# neue_schaltung.net
KiCad netlist of a schematic drawn in EAGLE
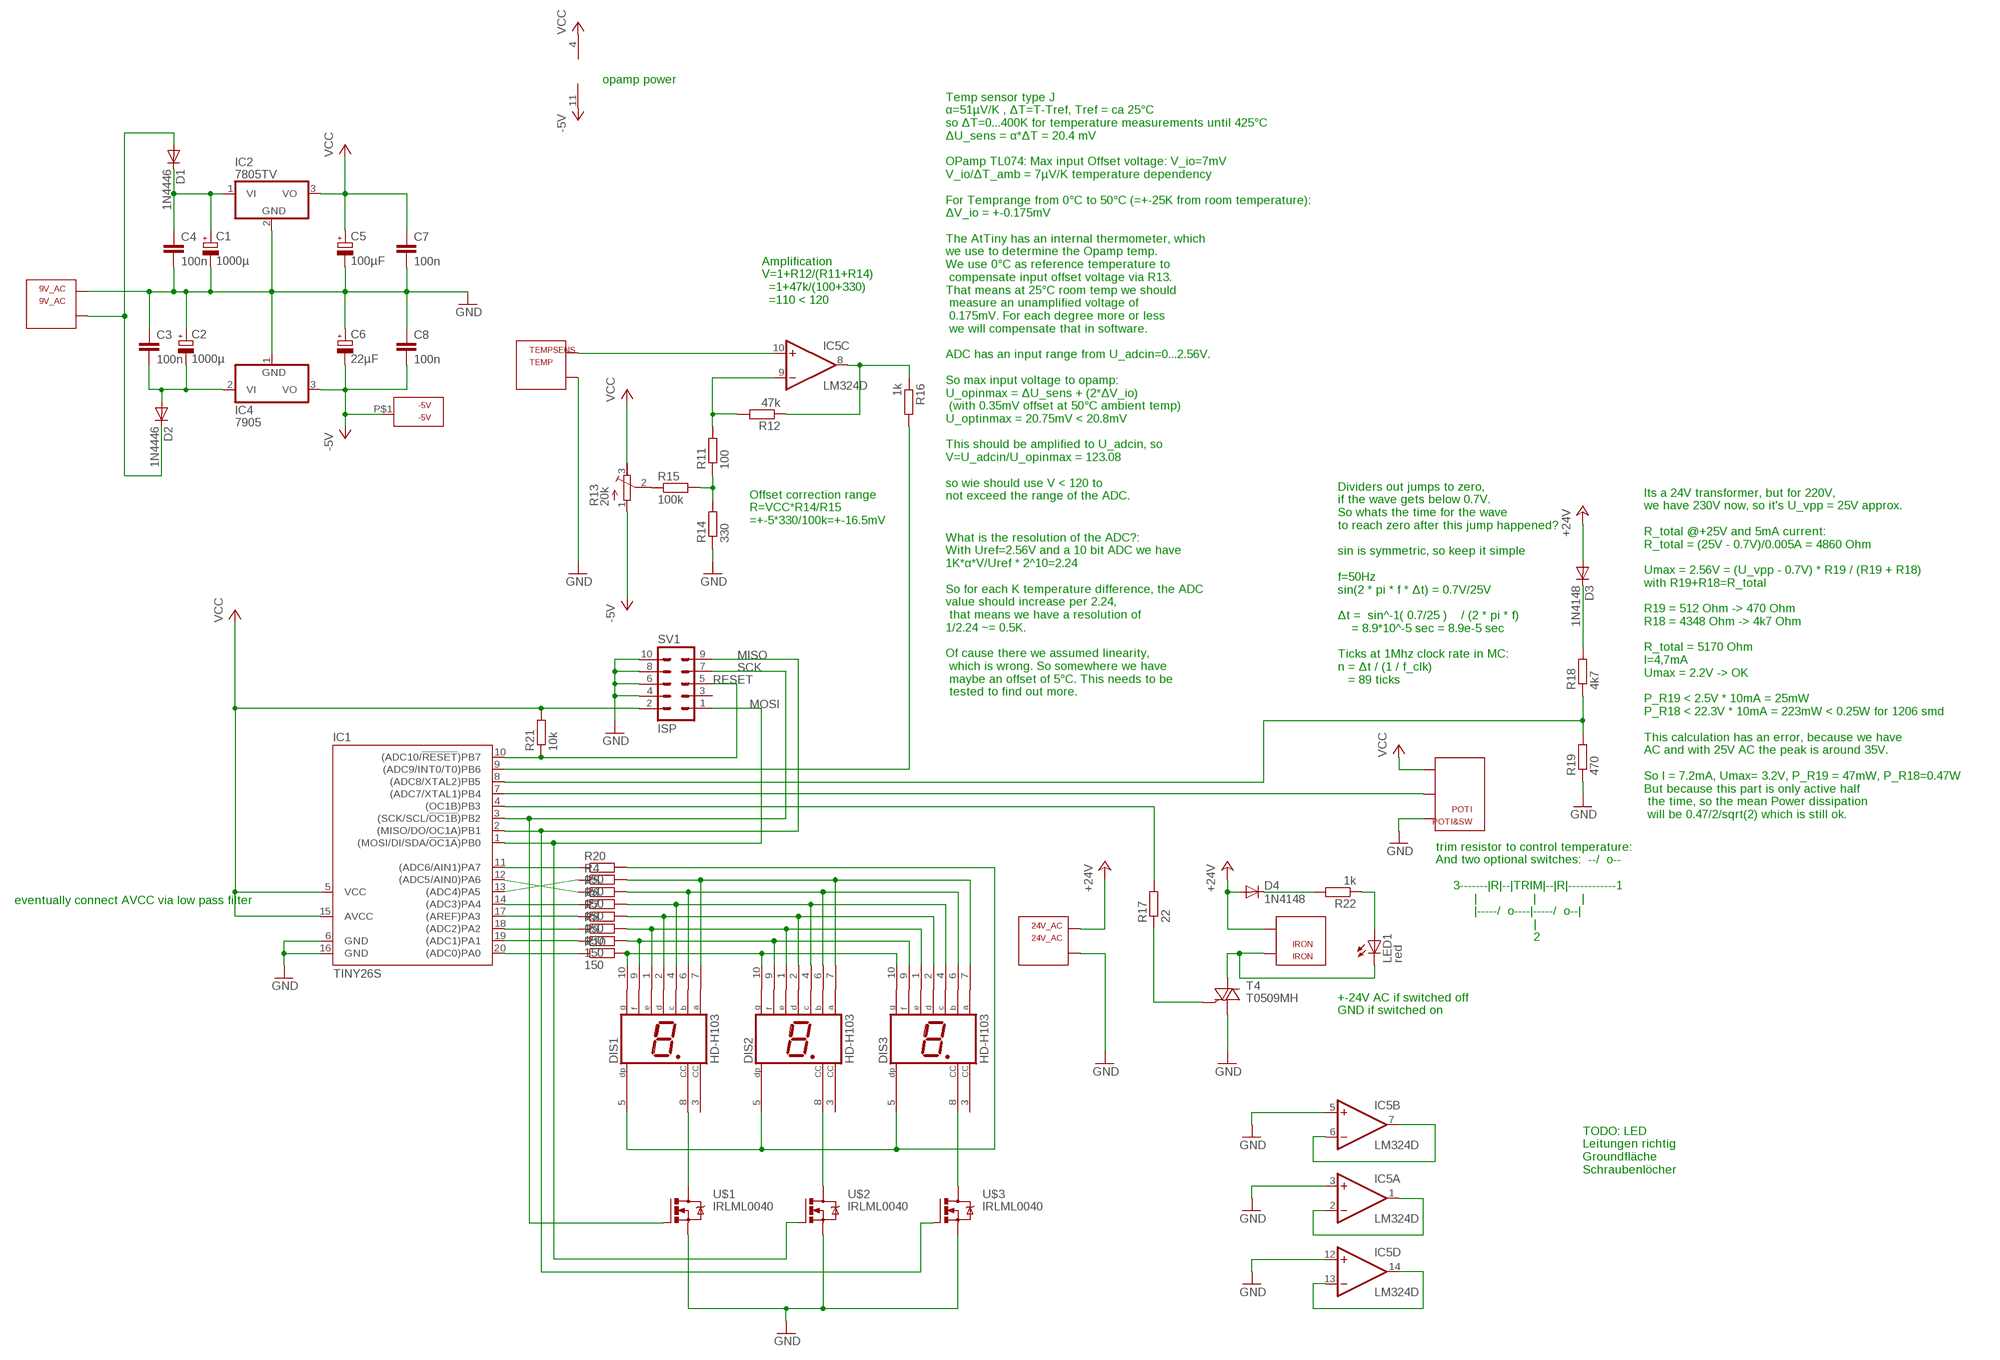
[diagram p0: schematic, sheet 1]

(export (version "E")
  (design (tool "Eeschema 10.0.6"))
  (components
    (comp (ref "-5V")
      (value "-5V")
      (footprint "eagle-import:WIREPAD_2H")
      (libsource (lib "eagle-import") (part "WIREPAD"))
    )
    (comp (ref "9V_AC")
      (value "9V_AC")
      (footprint "eagle-import:WIREPADX2_2H")
      (libsource (lib "eagle-import") (part "WIREPADX2"))
    )
    (comp (ref "24V_AC")
      (value "24V_AC")
      (footprint "eagle-import:WIREPADX2_2H_BIG")
      (libsource (lib "eagle-import") (part "WIREPADX2_BIG"))
    )
    (comp (ref "C1")
      (value "1000µ")
      (footprint "eagle-import:E5-10,5")
      (libsource (lib "eagle-import") (part "CPOL-EUE5-10.5"))
    )
    (comp (ref "C2")
      (value "1000µ")
      (footprint "eagle-import:E5-10,5")
      (libsource (lib "eagle-import") (part "CPOL-EUE5-10.5"))
    )
    (comp (ref "C3")
      (value "100n")
      (footprint "eagle-import:C0805")
      (libsource (lib "eagle-import") (part "C-EUC0805"))
    )
    (comp (ref "C4")
      (value "100n")
      (footprint "eagle-import:C0805")
      (libsource (lib "eagle-import") (part "C-EUC0805"))
    )
    (comp (ref "C5")
      (value "100µF")
      (footprint "eagle-import:E2-5")
      (libsource (lib "eagle-import") (part "CPOL-EUE2-5"))
    )
    (comp (ref "C6")
      (value "22µF")
      (footprint "eagle-import:E2-5")
      (libsource (lib "eagle-import") (part "CPOL-EUE2-5"))
    )
    (comp (ref "C7")
      (value "100n")
      (footprint "eagle-import:C0805")
      (libsource (lib "eagle-import") (part "C-EUC0805"))
    )
    (comp (ref "C8")
      (value "100n")
      (footprint "eagle-import:C0805")
      (libsource (lib "eagle-import") (part "C-EUC0805"))
    )
    (comp (ref "D1")
      (value "1N4446")
      (footprint "eagle-import:DO35-10")
      (libsource (lib "eagle-import") (part "1N4446"))
    )
    (comp (ref "D2")
      (value "1N4446")
      (footprint "eagle-import:DO35-10")
      (libsource (lib "eagle-import") (part "1N4446"))
    )
    (comp (ref "D3")
      (value "1N4148")
      (footprint "eagle-import:DO35-10")
      (libsource (lib "eagle-import") (part "1N4148DO35-10"))
    )
    (comp (ref "D4")
      (value "1N4148")
      (footprint "eagle-import:DO35-10")
      (libsource (lib "eagle-import") (part "1N4148DO35-10"))
    )
    (comp (ref "DIS1")
      (value "HD-H103")
      (footprint "eagle-import:HDSP-M")
      (libsource (lib "eagle-import") (part "HD-H103"))
    )
    (comp (ref "DIS2")
      (value "HD-H103")
      (footprint "eagle-import:HDSP-M")
      (libsource (lib "eagle-import") (part "HD-H103"))
    )
    (comp (ref "DIS3")
      (value "HD-H103")
      (footprint "eagle-import:HDSP-M")
      (libsource (lib "eagle-import") (part "HD-H103"))
    )
    (comp (ref "IC1")
      (value "TINY26S")
      (footprint "eagle-import:SO20L")
      (fields (field (name "MPN") "ATTINY261-20SU"))
      (libsource (lib "eagle-import") (part "TINY26S"))
    )
    (comp (ref "IC2")
      (value "7805TV")
      (footprint "eagle-import:TO220V")
      (libsource (lib "eagle-import") (part "78TV05"))
    )
    (comp (ref "IC4")
      (value "7905")
      (footprint "eagle-import:TO220H")
      (libsource (lib "eagle-import") (part "79T05"))
    )
    (comp (ref "IC5")
      (value "LM324D")
      (footprint "eagle-import:SO14")
      (libsource (lib "eagle-import") (part "LM324D"))
    )
    (comp (ref "IRON")
      (value "IRON")
      (footprint "eagle-import:WIREPADX2_2H_BIG")
      (libsource (lib "eagle-import") (part "WIREPADX2_BIG"))
    )
    (comp (ref "LED1")
      (value "red")
      (footprint "eagle-import:LED5MM")
      (libsource (lib "eagle-import") (part "LED5MM"))
    )
    (comp (ref "POTI&SW")
      (value "POTI")
      (footprint "eagle-import:WIREPADX3_2H")
      (libsource (lib "eagle-import") (part "WIREPADX3"))
    )
    (comp (ref "R4")
      (value "150")
      (footprint "eagle-import:M1206")
      (libsource (lib "eagle-import") (part "R-EU_M1206"))
    )
    (comp (ref "R5")
      (value "150")
      (footprint "eagle-import:M1206")
      (libsource (lib "eagle-import") (part "R-EU_M1206"))
    )
    (comp (ref "R6")
      (value "150")
      (footprint "eagle-import:M1206")
      (libsource (lib "eagle-import") (part "R-EU_M1206"))
    )
    (comp (ref "R7")
      (value "150")
      (footprint "eagle-import:M1206")
      (libsource (lib "eagle-import") (part "R-EU_M1206"))
    )
    (comp (ref "R8")
      (value "150")
      (footprint "eagle-import:M1206")
      (libsource (lib "eagle-import") (part "R-EU_M1206"))
    )
    (comp (ref "R9")
      (value "150")
      (footprint "eagle-import:M1206")
      (libsource (lib "eagle-import") (part "R-EU_M1206"))
    )
    (comp (ref "R10")
      (value "150")
      (footprint "eagle-import:M1206")
      (libsource (lib "eagle-import") (part "R-EU_M1206"))
    )
    (comp (ref "R11")
      (value "100")
      (footprint "eagle-import:M1206")
      (libsource (lib "eagle-import") (part "R-EU_M1206"))
    )
    (comp (ref "R12")
      (value "47k")
      (footprint "eagle-import:M1206")
      (libsource (lib "eagle-import") (part "R-EU_M1206"))
    )
    (comp (ref "R13")
      (value "20k")
      (footprint "eagle-import:RTRIM64W")
      (libsource (lib "eagle-import") (part "R-TRIMM64W"))
    )
    (comp (ref "R14")
      (value "330")
      (footprint "eagle-import:M1206")
      (libsource (lib "eagle-import") (part "R-EU_M1206"))
    )
    (comp (ref "R15")
      (value "100k")
      (footprint "eagle-import:M1206")
      (libsource (lib "eagle-import") (part "R-EU_M1206"))
    )
    (comp (ref "R16")
      (value "1k")
      (footprint "eagle-import:M1206")
      (libsource (lib "eagle-import") (part "R-EU_M1206"))
    )
    (comp (ref "R17")
      (value "22")
      (footprint "eagle-import:M1206")
      (libsource (lib "eagle-import") (part "R-EU_M1206"))
    )
    (comp (ref "R18")
      (value "4k7")
      (footprint "eagle-import:M1206")
      (libsource (lib "eagle-import") (part "R-EU_M1206"))
    )
    (comp (ref "R19")
      (value "470")
      (footprint "eagle-import:M1206")
      (libsource (lib "eagle-import") (part "R-EU_M1206"))
    )
    (comp (ref "R20")
      (value "150")
      (footprint "eagle-import:M1206")
      (libsource (lib "eagle-import") (part "R-EU_M1206"))
    )
    (comp (ref "R21")
      (value "10k")
      (footprint "eagle-import:M1206")
      (libsource (lib "eagle-import") (part "R-EU_M1206"))
    )
    (comp (ref "R22")
      (value "1k")
      (footprint "eagle-import:M1206")
      (libsource (lib "eagle-import") (part "R-EU_M1206"))
    )
    (comp (ref "SV1")
      (value "ISP")
      (footprint "eagle-import:ML10")
      (libsource (lib "eagle-import") (part "ML10"))
    )
    (comp (ref "T4")
      (value "T0509MH")
      (footprint "eagle-import:TO220AB")
      (libsource (lib "eagle-import") (part "BT136"))
    )
    (comp (ref "TEMPSENS")
      (value "TEMP")
      (footprint "eagle-import:WIREPADX2_2H")
      (libsource (lib "eagle-import") (part "WIREPADX2"))
    )
    (comp (ref "U$1")
      (value "IRLML0040")
      (footprint "eagle-import:MICRO3")
      (libsource (lib "eagle-import") (part "IRLML0040"))
    )
    (comp (ref "U$2")
      (value "IRLML0040")
      (footprint "eagle-import:MICRO3")
      (libsource (lib "eagle-import") (part "IRLML0040"))
    )
    (comp (ref "U$3")
      (value "IRLML0040")
      (footprint "eagle-import:MICRO3")
      (libsource (lib "eagle-import") (part "IRLML0040"))
    )
  )
  (nets
    (net (code "1") (name "+24V") (class "Default")
      (node (ref "24V_AC") (pin "P$1") (pinfunction "P$1_P$1") (pintype "bidirectional"))
      (node (ref "D3") (pin "A") (pinfunction "A_A") (pintype "passive"))
      (node (ref "D4") (pin "A") (pinfunction "A_A") (pintype "passive"))
      (node (ref "IRON") (pin "P$2") (pinfunction "P$2_P$2") (pintype "bidirectional"))
    )
    (net (code "2") (name "-5V") (class "Default")
      (node (ref "-5V") (pin "P$1") (pinfunction "P$1_P$1") (pintype "bidirectional"))
      (node (ref "C6") (pin "-") (pinfunction "-_-") (pintype "passive"))
      (node (ref "C8") (pin "2") (pinfunction "2_2") (pintype "passive"))
      (node (ref "IC4") (pin "3") (pinfunction "VO_3") (pintype "passive"))
      (node (ref "IC5") (pin "11") (pinfunction "V-_11") (pintype "power_in"))
      (node (ref "R13") (pin "1") (pinfunction "E_1") (pintype "passive"))
    )
    (net (code "3") (name "/MISO") (class "Default")
      (node (ref "IC1") (pin "2") (pinfunction "(MISO/DO/OC1A)PB1_2") (pintype "bidirectional"))
      (node (ref "SV1") (pin "9") (pinfunction "9_9") (pintype "passive"))
      (node (ref "U$3") (pin "1") (pinfunction "G_1") (pintype "passive"))
    )
    (net (code "4") (name "/MOSI") (class "Default")
      (node (ref "IC1") (pin "1") (pinfunction "(MOSI/DI/SDA/~{OC1A})PB0_1") (pintype "bidirectional"))
      (node (ref "SV1") (pin "1") (pinfunction "1_1") (pintype "passive"))
      (node (ref "U$2") (pin "1") (pinfunction "G_1") (pintype "passive"))
    )
    (net (code "5") (name "/RESET") (class "Default")
      (node (ref "IC1") (pin "10") (pinfunction "(ADC10/~{RESET})PB7_10") (pintype "bidirectional"))
      (node (ref "R21") (pin "1") (pinfunction "1_1") (pintype "passive"))
      (node (ref "SV1") (pin "5") (pinfunction "5_5") (pintype "passive"))
    )
    (net (code "6") (name "/SCK") (class "Default")
      (node (ref "IC1") (pin "3") (pinfunction "(SCK/SCL/~{OC1B})PB2_3") (pintype "bidirectional"))
      (node (ref "SV1") (pin "7") (pinfunction "7_7") (pintype "passive"))
      (node (ref "U$1") (pin "1") (pinfunction "G_1") (pintype "passive"))
    )
    (net (code "7") (name "GND") (class "Default")
      (node (ref "24V_AC") (pin "P$2") (pinfunction "P$2_P$2") (pintype "bidirectional"))
      (node (ref "9V_AC") (pin "P$1") (pinfunction "P$1_P$1") (pintype "bidirectional"))
      (node (ref "C1") (pin "-") (pinfunction "-_-") (pintype "passive"))
      (node (ref "C2") (pin "+") (pinfunction "+_+") (pintype "passive"))
      (node (ref "C3") (pin "1") (pinfunction "1_1") (pintype "passive"))
      (node (ref "C4") (pin "2") (pinfunction "2_2") (pintype "passive"))
      (node (ref "C5") (pin "-") (pinfunction "-_-") (pintype "passive"))
      (node (ref "C6") (pin "+") (pinfunction "+_+") (pintype "passive"))
      (node (ref "C7") (pin "2") (pinfunction "2_2") (pintype "passive"))
      (node (ref "C8") (pin "1") (pinfunction "1_1") (pintype "passive"))
      (node (ref "IC1") (pin "16") (pinfunction "GND_16") (pintype "power_in"))
      (node (ref "IC1") (pin "6") (pinfunction "GND_6") (pintype "power_in"))
      (node (ref "IC2") (pin "2") (pinfunction "GND_2") (pintype "passive"))
      (node (ref "IC4") (pin "1") (pinfunction "GND_1") (pintype "passive"))
      (node (ref "IC5") (pin "12") (pinfunction "+IN_12") (pintype "input"))
      (node (ref "IC5") (pin "3") (pinfunction "+IN_3") (pintype "input"))
      (node (ref "IC5") (pin "5") (pinfunction "+IN_5") (pintype "input"))
      (node (ref "POTI&SW") (pin "P$1") (pinfunction "P$1_P$1") (pintype "bidirectional"))
      (node (ref "R14") (pin "1") (pinfunction "1_1") (pintype "passive"))
      (node (ref "R19") (pin "1") (pinfunction "1_1") (pintype "passive"))
      (node (ref "SV1") (pin "10") (pinfunction "10_10") (pintype "passive"))
      (node (ref "SV1") (pin "4") (pinfunction "4_4") (pintype "passive"))
      (node (ref "SV1") (pin "6") (pinfunction "6_6") (pintype "passive"))
      (node (ref "SV1") (pin "8") (pinfunction "8_8") (pintype "passive"))
      (node (ref "T4") (pin "1") (pinfunction "A1_1") (pintype "passive"))
      (node (ref "TEMPSENS") (pin "P$2") (pinfunction "P$2_P$2") (pintype "bidirectional"))
      (node (ref "U$1") (pin "2") (pinfunction "S_2") (pintype "passive"))
      (node (ref "U$2") (pin "2") (pinfunction "S_2") (pintype "passive"))
      (node (ref "U$3") (pin "2") (pinfunction "S_2") (pintype "passive"))
    )
    (net (code "8") (name "Net-(9V_AC-PadP$2)") (class "Default")
      (node (ref "9V_AC") (pin "P$2") (pinfunction "P$2_P$2") (pintype "bidirectional"))
      (node (ref "D1") (pin "A") (pinfunction "A_A") (pintype "passive"))
      (node (ref "D2") (pin "C") (pinfunction "C_C") (pintype "passive"))
    )
    (net (code "9") (name "Net-(D3-PadC)") (class "Default")
      (node (ref "D3") (pin "C") (pinfunction "C_C") (pintype "passive"))
      (node (ref "R18") (pin "2") (pinfunction "2_2") (pintype "passive"))
    )
    (net (code "10") (name "Net-(D4-PadC)") (class "Default")
      (node (ref "D4") (pin "C") (pinfunction "C_C") (pintype "passive"))
      (node (ref "R22") (pin "2") (pinfunction "2_2") (pintype "passive"))
    )
    (net (code "11") (name "Net-(DIS1-A)") (class "Default")
      (node (ref "DIS1") (pin "7") (pinfunction "A_7") (pintype "passive"))
      (node (ref "DIS2") (pin "7") (pinfunction "A_7") (pintype "passive"))
      (node (ref "DIS3") (pin "7") (pinfunction "A_7") (pintype "passive"))
      (node (ref "R4") (pin "2") (pinfunction "2_2") (pintype "passive"))
    )
    (net (code "12") (name "Net-(DIS1-B)") (class "Default")
      (node (ref "DIS1") (pin "6") (pinfunction "B_6") (pintype "passive"))
      (node (ref "DIS2") (pin "6") (pinfunction "B_6") (pintype "passive"))
      (node (ref "DIS3") (pin "6") (pinfunction "B_6") (pintype "passive"))
      (node (ref "R5") (pin "2") (pinfunction "2_2") (pintype "passive"))
    )
    (net (code "13") (name "Net-(DIS1-C)") (class "Default")
      (node (ref "DIS1") (pin "4") (pinfunction "C_4") (pintype "passive"))
      (node (ref "DIS2") (pin "4") (pinfunction "C_4") (pintype "passive"))
      (node (ref "DIS3") (pin "4") (pinfunction "C_4") (pintype "passive"))
      (node (ref "R6") (pin "2") (pinfunction "2_2") (pintype "passive"))
    )
    (net (code "14") (name "Net-(DIS1-D)") (class "Default")
      (node (ref "DIS1") (pin "2") (pinfunction "D_2") (pintype "passive"))
      (node (ref "DIS2") (pin "2") (pinfunction "D_2") (pintype "passive"))
      (node (ref "DIS3") (pin "2") (pinfunction "D_2") (pintype "passive"))
      (node (ref "R7") (pin "2") (pinfunction "2_2") (pintype "passive"))
    )
    (net (code "15") (name "Net-(DIS1-DP)") (class "Default")
      (node (ref "DIS1") (pin "5") (pinfunction "DP_5") (pintype "passive"))
      (node (ref "DIS2") (pin "5") (pinfunction "DP_5") (pintype "passive"))
      (node (ref "DIS3") (pin "5") (pinfunction "DP_5") (pintype "passive"))
      (node (ref "R20") (pin "2") (pinfunction "2_2") (pintype "passive"))
    )
    (net (code "16") (name "Net-(DIS1-E)") (class "Default")
      (node (ref "DIS1") (pin "1") (pinfunction "E_1") (pintype "passive"))
      (node (ref "DIS2") (pin "1") (pinfunction "E_1") (pintype "passive"))
      (node (ref "DIS3") (pin "1") (pinfunction "E_1") (pintype "passive"))
      (node (ref "R8") (pin "2") (pinfunction "2_2") (pintype "passive"))
    )
    (net (code "17") (name "Net-(DIS1-F)") (class "Default")
      (node (ref "DIS1") (pin "9") (pinfunction "F_9") (pintype "passive"))
      (node (ref "DIS2") (pin "9") (pinfunction "F_9") (pintype "passive"))
      (node (ref "DIS3") (pin "9") (pinfunction "F_9") (pintype "passive"))
      (node (ref "R9") (pin "2") (pinfunction "2_2") (pintype "passive"))
    )
    (net (code "18") (name "Net-(DIS1-G)") (class "Default")
      (node (ref "DIS1") (pin "10") (pinfunction "G_10") (pintype "passive"))
      (node (ref "DIS2") (pin "10") (pinfunction "G_10") (pintype "passive"))
      (node (ref "DIS3") (pin "10") (pinfunction "G_10") (pintype "passive"))
      (node (ref "R10") (pin "2") (pinfunction "2_2") (pintype "passive"))
    )
    (net (code "19") (name "Net-(IC1-(ADC0)PA0)") (class "Default")
      (node (ref "IC1") (pin "20") (pinfunction "(ADC0)PA0_20") (pintype "bidirectional"))
      (node (ref "R10") (pin "1") (pinfunction "1_1") (pintype "passive"))
    )
    (net (code "20") (name "Net-(IC1-(ADC1)PA1)") (class "Default")
      (node (ref "IC1") (pin "19") (pinfunction "(ADC1)PA1_19") (pintype "bidirectional"))
      (node (ref "R9") (pin "1") (pinfunction "1_1") (pintype "passive"))
    )
    (net (code "21") (name "Net-(IC1-(ADC2)PA2)") (class "Default")
      (node (ref "IC1") (pin "18") (pinfunction "(ADC2)PA2_18") (pintype "bidirectional"))
      (node (ref "R8") (pin "1") (pinfunction "1_1") (pintype "passive"))
    )
    (net (code "22") (name "Net-(IC1-(ADC3)PA4)") (class "Default")
      (node (ref "IC1") (pin "14") (pinfunction "(ADC3)PA4_14") (pintype "bidirectional"))
      (node (ref "R6") (pin "1") (pinfunction "1_1") (pintype "passive"))
    )
    (net (code "23") (name "Net-(IC1-(ADC4)PA5)") (class "Default")
      (node (ref "IC1") (pin "13") (pinfunction "(ADC4)PA5_13") (pintype "bidirectional"))
      (node (ref "R4") (pin "1") (pinfunction "1_1") (pintype "passive"))
    )
    (net (code "24") (name "Net-(IC1-(ADC5{slash}AIN0)PA6)") (class "Default")
      (node (ref "IC1") (pin "12") (pinfunction "(ADC5/AIN0)PA6_12") (pintype "bidirectional"))
      (node (ref "R5") (pin "1") (pinfunction "1_1") (pintype "passive"))
    )
    (net (code "25") (name "Net-(IC1-(ADC6{slash}AIN1)PA7)") (class "Default")
      (node (ref "IC1") (pin "11") (pinfunction "(ADC6/AIN1)PA7_11") (pintype "bidirectional"))
      (node (ref "R20") (pin "1") (pinfunction "1_1") (pintype "passive"))
    )
    (net (code "26") (name "Net-(IC1-(ADC7{slash}XTAL1)PB4)") (class "Default")
      (node (ref "IC1") (pin "7") (pinfunction "(ADC7/XTAL1)PB4_7") (pintype "bidirectional"))
      (node (ref "POTI&SW") (pin "P$2") (pinfunction "P$2_P$2") (pintype "bidirectional"))
    )
    (net (code "27") (name "Net-(IC1-(ADC8{slash}XTAL2)PB5)") (class "Default")
      (node (ref "IC1") (pin "8") (pinfunction "(ADC8/XTAL2)PB5_8") (pintype "bidirectional"))
      (node (ref "R18") (pin "1") (pinfunction "1_1") (pintype "passive"))
      (node (ref "R19") (pin "2") (pinfunction "2_2") (pintype "passive"))
    )
    (net (code "28") (name "Net-(IC1-(ADC9{slash}INT0{slash}T0)PB6)") (class "Default")
      (node (ref "IC1") (pin "9") (pinfunction "(ADC9/INT0/T0)PB6_9") (pintype "bidirectional"))
      (node (ref "R16") (pin "2") (pinfunction "2_2") (pintype "passive"))
    )
    (net (code "29") (name "Net-(IC1-(AREF)PA3)") (class "Default")
      (node (ref "IC1") (pin "17") (pinfunction "(AREF)PA3_17") (pintype "bidirectional"))
      (node (ref "R7") (pin "1") (pinfunction "1_1") (pintype "passive"))
    )
    (net (code "30") (name "Net-(IC1-(OC1B)PB3)") (class "Default")
      (node (ref "IC1") (pin "4") (pinfunction "(OC1B)PB3_4") (pintype "bidirectional"))
      (node (ref "R17") (pin "2") (pinfunction "2_2") (pintype "passive"))
    )
    (net (code "31") (name "Net-(IC2-VI)") (class "Default")
      (node (ref "C1") (pin "+") (pinfunction "+_+") (pintype "passive"))
      (node (ref "C4") (pin "1") (pinfunction "1_1") (pintype "passive"))
      (node (ref "D1") (pin "C") (pinfunction "C_C") (pintype "passive"))
      (node (ref "IC2") (pin "1") (pinfunction "VI_1") (pintype "input"))
    )
    (net (code "32") (name "Net-(IC4-VI)") (class "Default")
      (node (ref "C2") (pin "-") (pinfunction "-_-") (pintype "passive"))
      (node (ref "C3") (pin "2") (pinfunction "2_2") (pintype "passive"))
      (node (ref "D2") (pin "A") (pinfunction "A_A") (pintype "passive"))
      (node (ref "IC4") (pin "2") (pinfunction "VI_2") (pintype "input"))
    )
    (net (code "33") (name "Net-(IC5A--IN)") (class "Default")
      (node (ref "IC5") (pin "1") (pinfunction "OUT_1") (pintype "output"))
      (node (ref "IC5") (pin "2") (pinfunction "-IN_2") (pintype "input"))
    )
    (net (code "34") (name "Net-(IC5B--IN)") (class "Default")
      (node (ref "IC5") (pin "6") (pinfunction "-IN_6") (pintype "input"))
      (node (ref "IC5") (pin "7") (pinfunction "OUT_7") (pintype "output"))
    )
    (net (code "35") (name "Net-(IC5C-+IN)") (class "Default")
      (node (ref "IC5") (pin "10") (pinfunction "+IN_10") (pintype "input"))
      (node (ref "TEMPSENS") (pin "P$1") (pinfunction "P$1_P$1") (pintype "bidirectional"))
    )
    (net (code "36") (name "Net-(IC5C--IN)") (class "Default")
      (node (ref "IC5") (pin "9") (pinfunction "-IN_9") (pintype "input"))
      (node (ref "R11") (pin "2") (pinfunction "2_2") (pintype "passive"))
      (node (ref "R12") (pin "2") (pinfunction "2_2") (pintype "passive"))
    )
    (net (code "37") (name "Net-(IC5C-OUT)") (class "Default")
      (node (ref "IC5") (pin "8") (pinfunction "OUT_8") (pintype "output"))
      (node (ref "R12") (pin "1") (pinfunction "1_1") (pintype "passive"))
      (node (ref "R16") (pin "1") (pinfunction "1_1") (pintype "passive"))
    )
    (net (code "38") (name "Net-(IC5D--IN)") (class "Default")
      (node (ref "IC5") (pin "13") (pinfunction "-IN_13") (pintype "input"))
      (node (ref "IC5") (pin "14") (pinfunction "OUT_14") (pintype "output"))
    )
    (net (code "39") (name "Net-(LED1-C)") (class "Default")
      (node (ref "IRON") (pin "P$1") (pinfunction "P$1_P$1") (pintype "bidirectional"))
      (node (ref "LED1") (pin "K") (pinfunction "C_K") (pintype "passive"))
      (node (ref "T4") (pin "2") (pinfunction "A2_2") (pintype "passive"))
    )
    (net (code "40") (name "Net-(LED1-PadA)") (class "Default")
      (node (ref "LED1") (pin "A") (pinfunction "A_A") (pintype "passive"))
      (node (ref "R22") (pin "1") (pinfunction "1_1") (pintype "passive"))
    )
    (net (code "41") (name "Net-(R11-Pad1)") (class "Default")
      (node (ref "R11") (pin "1") (pinfunction "1_1") (pintype "passive"))
      (node (ref "R14") (pin "2") (pinfunction "2_2") (pintype "passive"))
      (node (ref "R15") (pin "2") (pinfunction "2_2") (pintype "passive"))
    )
    (net (code "42") (name "Net-(R13-S)") (class "Default")
      (node (ref "R13") (pin "2") (pinfunction "S_2") (pintype "passive"))
      (node (ref "R15") (pin "1") (pinfunction "1_1") (pintype "passive"))
    )
    (net (code "43") (name "Net-(T4-G)") (class "Default")
      (node (ref "R17") (pin "1") (pinfunction "1_1") (pintype "passive"))
      (node (ref "T4") (pin "3") (pinfunction "G_3") (pintype "passive"))
    )
    (net (code "44") (name "Net-(U$1-D)") (class "Default")
      (node (ref "DIS1") (pin "8") (pinfunction "CC_8") (pintype "passive"))
      (node (ref "U$1") (pin "3") (pinfunction "D_3") (pintype "passive"))
    )
    (net (code "45") (name "Net-(U$2-D)") (class "Default")
      (node (ref "DIS2") (pin "8") (pinfunction "CC_8") (pintype "passive"))
      (node (ref "U$2") (pin "3") (pinfunction "D_3") (pintype "passive"))
    )
    (net (code "46") (name "Net-(U$3-D)") (class "Default")
      (node (ref "DIS3") (pin "8") (pinfunction "CC_8") (pintype "passive"))
      (node (ref "U$3") (pin "3") (pinfunction "D_3") (pintype "passive"))
    )
    (net (code "47") (name "VCC") (class "Default")
      (node (ref "C5") (pin "+") (pinfunction "+_+") (pintype "passive"))
      (node (ref "C7") (pin "1") (pinfunction "1_1") (pintype "passive"))
      (node (ref "IC1") (pin "15") (pinfunction "AVCC_15") (pintype "power_in"))
      (node (ref "IC1") (pin "5") (pinfunction "VCC_5") (pintype "power_in"))
      (node (ref "IC2") (pin "3") (pinfunction "VO_3") (pintype "passive"))
      (node (ref "IC5") (pin "4") (pinfunction "V+_4") (pintype "power_in"))
      (node (ref "POTI&SW") (pin "P$3") (pinfunction "P$3_P$3") (pintype "bidirectional"))
      (node (ref "R13") (pin "3") (pinfunction "A_3") (pintype "passive"))
      (node (ref "R21") (pin "2") (pinfunction "2_2") (pintype "passive"))
      (node (ref "SV1") (pin "2") (pinfunction "2_2") (pintype "passive"))
    )
    (net (code "48") (name "unconnected-(DIS1-CC-Pad3)") (class "Default")
      (node (ref "DIS1") (pin "3") (pinfunction "CC_3") (pintype "passive"))
    )
    (net (code "49") (name "unconnected-(DIS2-CC-Pad3)") (class "Default")
      (node (ref "DIS2") (pin "3") (pinfunction "CC_3") (pintype "passive"))
    )
    (net (code "50") (name "unconnected-(DIS3-CC-Pad3)") (class "Default")
      (node (ref "DIS3") (pin "3") (pinfunction "CC_3") (pintype "passive"))
    )
    (net (code "51") (name "unconnected-(SV1-Pad3)") (class "Default")
      (node (ref "SV1") (pin "3") (pinfunction "3_3") (pintype "passive"))
    )
  )
)
